# G8MainA_99_5x31.net
KiCad netlist of a schematic drawn in EAGLE
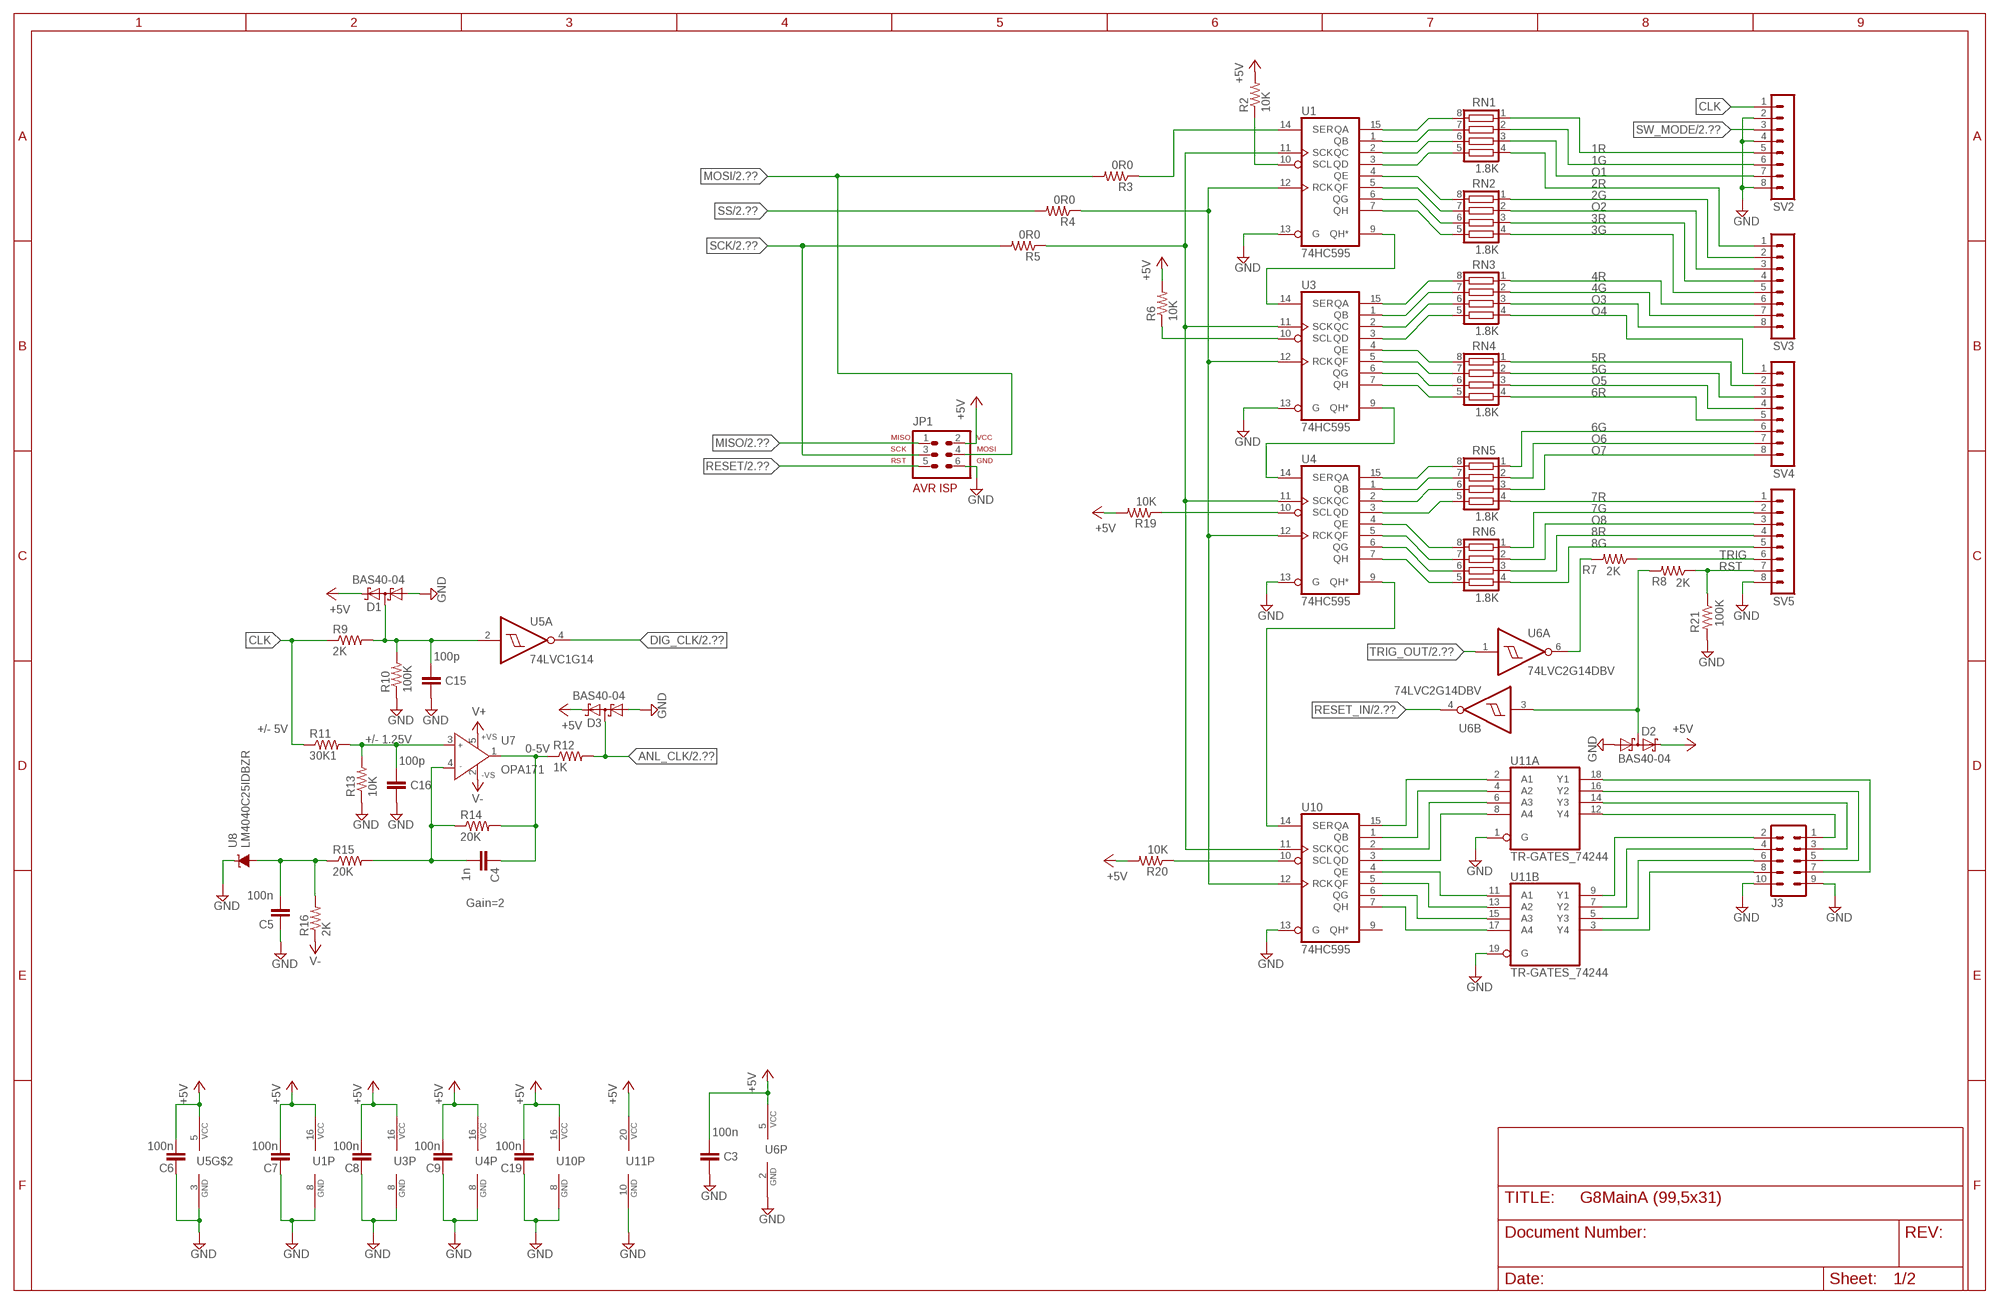
[diagram p0: schematic, sheet 1]
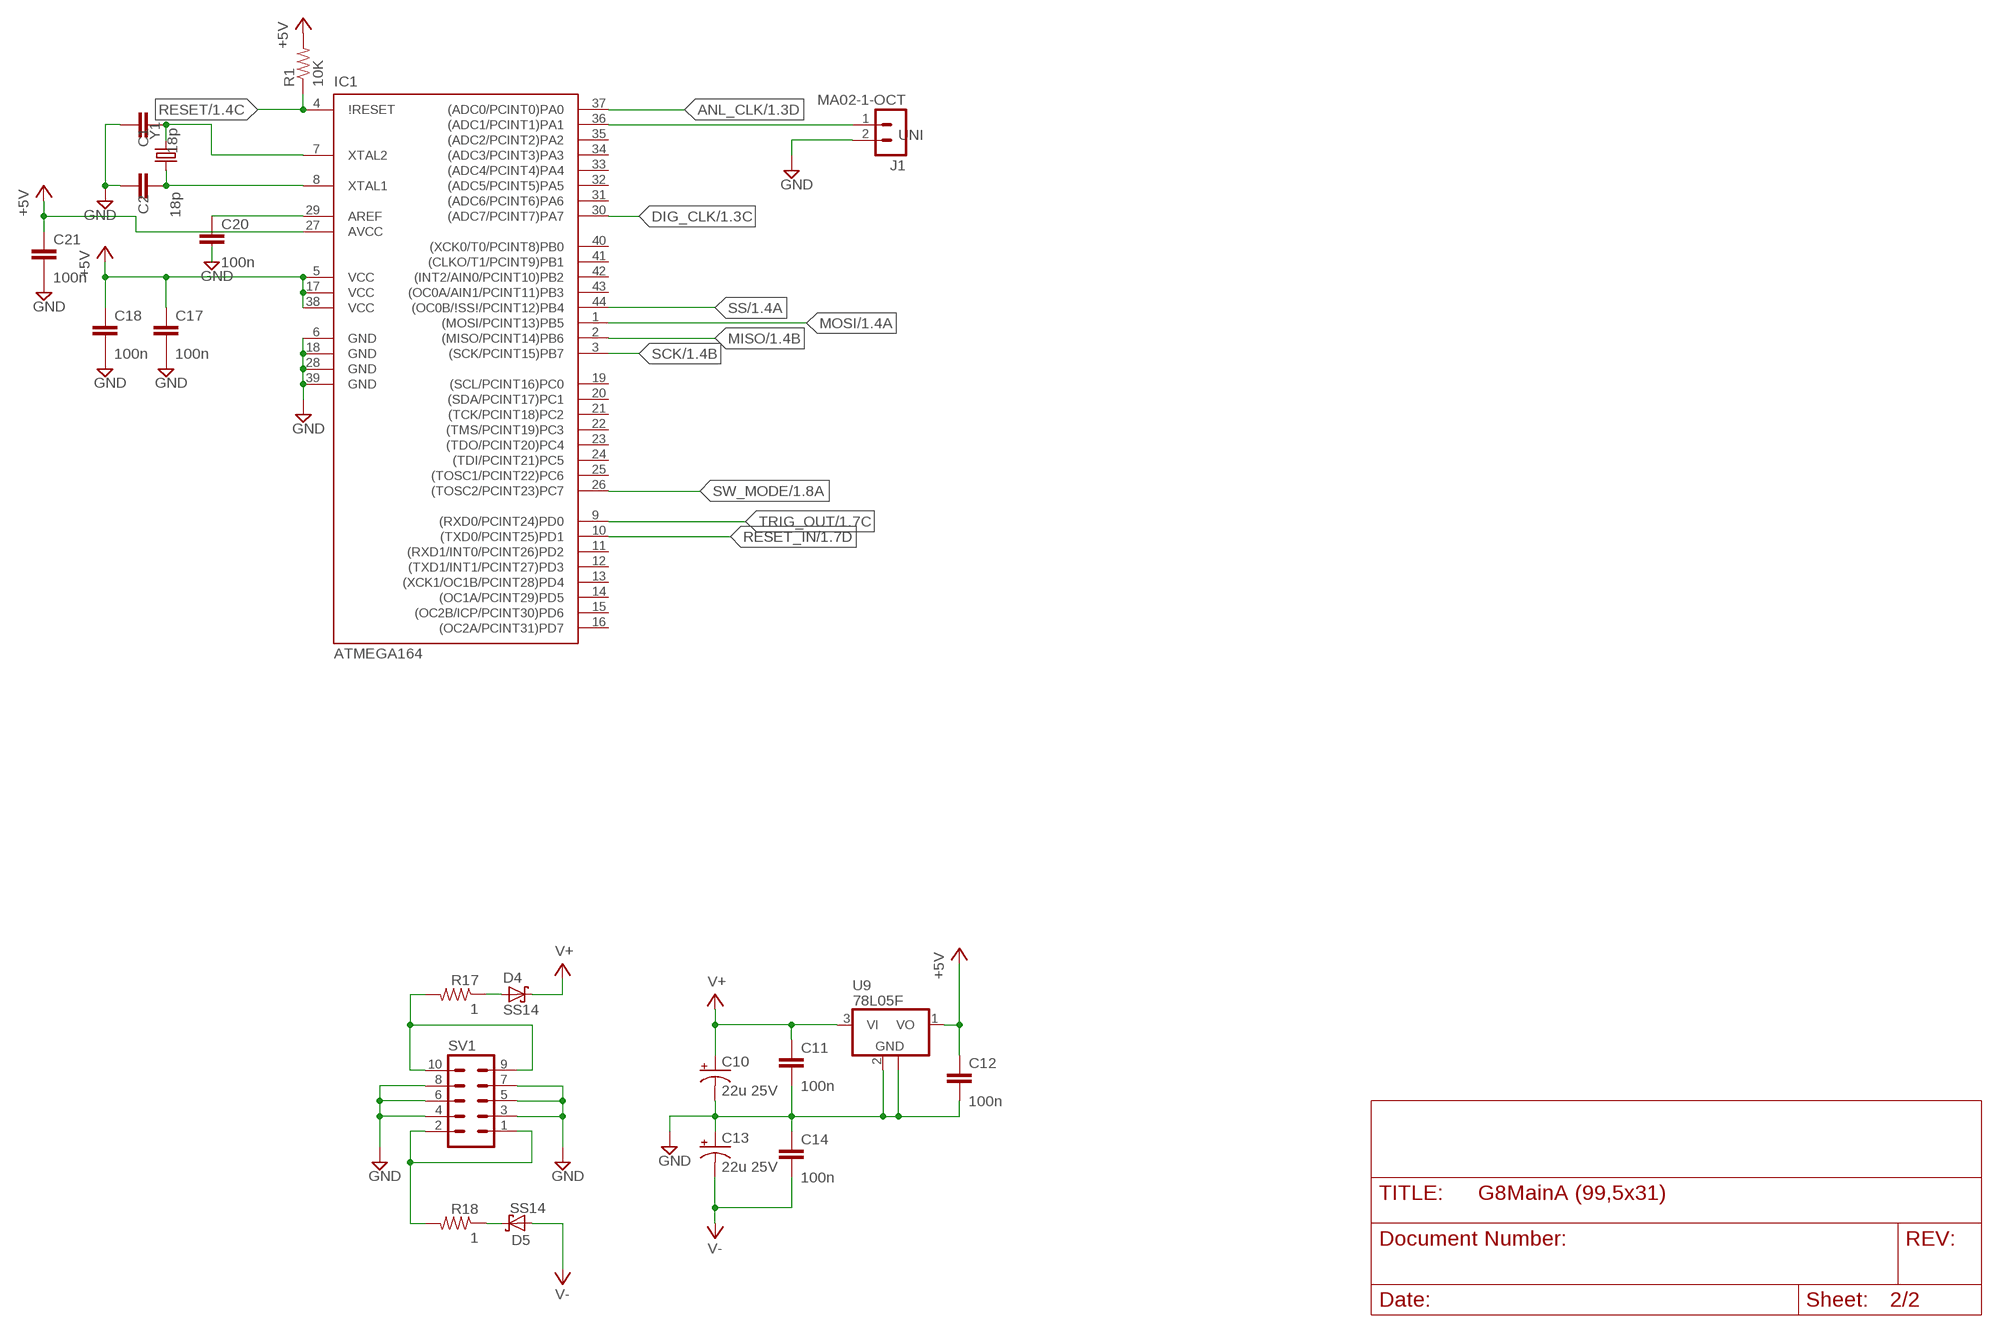
[diagram p1: schematic, sheet 2]

(export (version "E")
  (design (tool "Eeschema 10.0.6"))
  (components
    (comp (ref "C1")
      (value "18p")
      (footprint "eagle-import:C0603")
      (libsource (lib "eagle-import") (part "C0603"))
    )
    (comp (ref "C2")
      (value "18p")
      (footprint "eagle-import:C0603")
      (libsource (lib "eagle-import") (part "C0603"))
    )
    (comp (ref "C10")
      (value "22u 25V")
      (footprint "eagle-import:PANASONIC_C")
      (libsource (lib "eagle-import") (part "CPOL-USC"))
    )
    (comp (ref "C11")
      (value "100n")
      (footprint "eagle-import:C0603")
      (libsource (lib "eagle-import") (part "C0603"))
    )
    (comp (ref "C12")
      (value "100n")
      (footprint "eagle-import:C0603")
      (libsource (lib "eagle-import") (part "C0603"))
    )
    (comp (ref "C13")
      (value "22u 25V")
      (footprint "eagle-import:PANASONIC_C")
      (libsource (lib "eagle-import") (part "CPOL-USC"))
    )
    (comp (ref "C14")
      (value "100n")
      (footprint "eagle-import:C0603")
      (libsource (lib "eagle-import") (part "C0603"))
    )
    (comp (ref "C17")
      (value "100n")
      (footprint "eagle-import:C0603")
      (libsource (lib "eagle-import") (part "C0603"))
    )
    (comp (ref "C18")
      (value "100n")
      (footprint "eagle-import:C0603")
      (libsource (lib "eagle-import") (part "C0603"))
    )
    (comp (ref "C20")
      (value "100n")
      (footprint "eagle-import:C0603")
      (libsource (lib "eagle-import") (part "C0603"))
    )
    (comp (ref "C21")
      (value "100n")
      (footprint "eagle-import:C0603")
      (libsource (lib "eagle-import") (part "C0603"))
    )
    (comp (ref "D4")
      (value "SS14")
      (footprint "eagle-import:SMA-DO214AC")
      (libsource (lib "eagle-import") (part "T100331"))
    )
    (comp (ref "D5")
      (value "SS14")
      (footprint "eagle-import:SMA-DO214AC")
      (libsource (lib "eagle-import") (part "T100331"))
    )
    (comp (ref "IC1")
      (value "ATMEGA164")
      (footprint "eagle-import:TQFP44")
      (libsource (lib "eagle-import") (part "MEGA164P/324P/644P-AU"))
    )
    (comp (ref "J1")
      (value "MA02-1-OCT")
      (footprint "eagle-import:MA02-1-OCT")
      (libsource (lib "eagle-import") (part "MA02-1-OCT"))
    )
    (comp (ref "R1")
      (value "10K")
      (footprint "eagle-import:R0603")
      (libsource (lib "eagle-import") (part "R0603"))
    )
    (comp (ref "R17")
      (value "1")
      (footprint "eagle-import:R0603")
      (libsource (lib "eagle-import") (part "R0603"))
    )
    (comp (ref "R18")
      (value "1")
      (footprint "eagle-import:R0603")
      (libsource (lib "eagle-import") (part "R0603"))
    )
    (comp (ref "SV1")
      (value "MA05-2")
      (footprint "eagle-import:MA05-2")
      (libsource (lib "eagle-import") (part "MA05-2"))
    )
    (comp (ref "U9")
      (value "78L05F")
      (footprint "eagle-import:SOT89")
      (libsource (lib "eagle-import") (part "78LF05"))
    )
    (comp (ref "Y1")
      (value "CRYSTALHC49UV")
      (footprint "eagle-import:HC49U-V")
      (libsource (lib "eagle-import") (part "CRYSTALHC49UV"))
    )
    (comp (ref "C3")
      (value "100n")
      (footprint "eagle-import:C0603")
      (libsource (lib "eagle-import") (part "C0603"))
    )
    (comp (ref "C4")
      (value "1n")
      (footprint "eagle-import:C0603")
      (libsource (lib "eagle-import") (part "C0603"))
    )
    (comp (ref "C5")
      (value "100n")
      (footprint "eagle-import:C0603")
      (libsource (lib "eagle-import") (part "C0603"))
    )
    (comp (ref "C6")
      (value "100n")
      (footprint "eagle-import:C0603")
      (libsource (lib "eagle-import") (part "C0603"))
    )
    (comp (ref "C7")
      (value "100n")
      (footprint "eagle-import:C0603")
      (libsource (lib "eagle-import") (part "C0603"))
    )
    (comp (ref "C8")
      (value "100n")
      (footprint "eagle-import:C0603")
      (libsource (lib "eagle-import") (part "C0603"))
    )
    (comp (ref "C9")
      (value "100n")
      (footprint "eagle-import:C0603")
      (libsource (lib "eagle-import") (part "C0603"))
    )
    (comp (ref "C15")
      (value "100p")
      (footprint "eagle-import:C0603")
      (libsource (lib "eagle-import") (part "C0603"))
    )
    (comp (ref "C16")
      (value "100p")
      (footprint "eagle-import:C0603")
      (libsource (lib "eagle-import") (part "C0603"))
    )
    (comp (ref "C19")
      (value "100n")
      (footprint "eagle-import:C0603")
      (libsource (lib "eagle-import") (part "C0603"))
    )
    (comp (ref "D1")
      (value "BAS40-04")
      (footprint "eagle-import:SOT23")
      (libsource (lib "eagle-import") (part "BAS40-04"))
    )
    (comp (ref "D2")
      (value "BAS40-04")
      (footprint "eagle-import:SOT23")
      (libsource (lib "eagle-import") (part "BAS40-04"))
    )
    (comp (ref "D3")
      (value "BAS40-04")
      (footprint "eagle-import:SOT23")
      (libsource (lib "eagle-import") (part "BAS40-04"))
    )
    (comp (ref "J3")
      (value "MA05-2")
      (footprint "eagle-import:MA05-2")
      (libsource (lib "eagle-import") (part "MA05-2"))
    )
    (comp (ref "JP1")
      (value "AVR-ISP-6VERT")
      (footprint "eagle-import:AVR-ISP-6")
      (libsource (lib "eagle-import") (part "AVR-ISP-6VERT"))
    )
    (comp (ref "R2")
      (value "10K")
      (footprint "eagle-import:R0603")
      (libsource (lib "eagle-import") (part "R0603"))
    )
    (comp (ref "R3")
      (value "0R0")
      (footprint "eagle-import:R0603")
      (libsource (lib "eagle-import") (part "R0603"))
    )
    (comp (ref "R4")
      (value "0R0")
      (footprint "eagle-import:R0603")
      (libsource (lib "eagle-import") (part "R0603"))
    )
    (comp (ref "R5")
      (value "0R0")
      (footprint "eagle-import:R0603")
      (libsource (lib "eagle-import") (part "R0603"))
    )
    (comp (ref "R6")
      (value "10K")
      (footprint "eagle-import:R0603")
      (libsource (lib "eagle-import") (part "R0603"))
    )
    (comp (ref "R7")
      (value "2K")
      (footprint "eagle-import:R0603")
      (libsource (lib "eagle-import") (part "R0603"))
    )
    (comp (ref "R8")
      (value "2K")
      (footprint "eagle-import:R0603")
      (libsource (lib "eagle-import") (part "R0603"))
    )
    (comp (ref "R9")
      (value "2K")
      (footprint "eagle-import:R0603")
      (libsource (lib "eagle-import") (part "R0603"))
    )
    (comp (ref "R10")
      (value "100K")
      (footprint "eagle-import:R0603")
      (libsource (lib "eagle-import") (part "R0603"))
    )
    (comp (ref "R11")
      (value "30K1")
      (footprint "eagle-import:R0603")
      (libsource (lib "eagle-import") (part "R0603"))
    )
    (comp (ref "R12")
      (value "1K")
      (footprint "eagle-import:R0603")
      (libsource (lib "eagle-import") (part "R0603"))
    )
    (comp (ref "R13")
      (value "10K")
      (footprint "eagle-import:R0603")
      (libsource (lib "eagle-import") (part "R0603"))
    )
    (comp (ref "R14")
      (value "20K")
      (footprint "eagle-import:R0603")
      (libsource (lib "eagle-import") (part "R0603"))
    )
    (comp (ref "R15")
      (value "20K")
      (footprint "eagle-import:R0603")
      (libsource (lib "eagle-import") (part "R0603"))
    )
    (comp (ref "R16")
      (value "2K")
      (footprint "eagle-import:R0603")
      (libsource (lib "eagle-import") (part "R0603"))
    )
    (comp (ref "R19")
      (value "10K")
      (footprint "eagle-import:R0603")
      (libsource (lib "eagle-import") (part "R0603"))
    )
    (comp (ref "R20")
      (value "10K")
      (footprint "eagle-import:R0603")
      (libsource (lib "eagle-import") (part "R0603"))
    )
    (comp (ref "R21")
      (value "100K")
      (footprint "eagle-import:R0603")
      (libsource (lib "eagle-import") (part "R0603"))
    )
    (comp (ref "RN1")
      (value "1.8K")
      (footprint "eagle-import:CTS742C083")
      (libsource (lib "eagle-import") (part "CTS742C083"))
    )
    (comp (ref "RN2")
      (value "1.8K")
      (footprint "eagle-import:CTS742C083")
      (libsource (lib "eagle-import") (part "CTS742C083"))
    )
    (comp (ref "RN3")
      (value "1.8K")
      (footprint "eagle-import:CTS742C083")
      (libsource (lib "eagle-import") (part "CTS742C083"))
    )
    (comp (ref "RN4")
      (value "1.8K")
      (footprint "eagle-import:CTS742C083")
      (libsource (lib "eagle-import") (part "CTS742C083"))
    )
    (comp (ref "RN5")
      (value "1.8K")
      (footprint "eagle-import:CTS742C083")
      (fields (field (name "OC_FARNELL") "unknown") (field (name "OC_NEWARK") "unknown"))
      (libsource (lib "eagle-import") (part "CTS742C083"))
    )
    (comp (ref "RN6")
      (value "1.8K")
      (footprint "eagle-import:CTS742C083")
      (fields (field (name "OC_FARNELL") "unknown") (field (name "OC_NEWARK") "unknown"))
      (libsource (lib "eagle-import") (part "CTS742C083"))
    )
    (comp (ref "SV2")
      (value "MA08-1-O")
      (footprint "eagle-import:MA08-OCT")
      (libsource (lib "eagle-import") (part "MA08-1-O"))
    )
    (comp (ref "SV3")
      (value "MA08-1-O")
      (footprint "eagle-import:MA08-OCT")
      (libsource (lib "eagle-import") (part "MA08-1-O"))
    )
    (comp (ref "SV4")
      (value "MA08-1-O")
      (footprint "eagle-import:MA08-OCT")
      (libsource (lib "eagle-import") (part "MA08-1-O"))
    )
    (comp (ref "SV5")
      (value "MA08-1-O")
      (footprint "eagle-import:MA08-OCT")
      (libsource (lib "eagle-import") (part "MA08-1-O"))
    )
    (comp (ref "U1")
      (value "74HC595")
      (footprint "eagle-import:TSSOP16")
      (libsource (lib "eagle-import") (part "74595DT"))
    )
    (comp (ref "U3")
      (value "74HC595")
      (footprint "eagle-import:TSSOP16")
      (libsource (lib "eagle-import") (part "74595DT"))
    )
    (comp (ref "U4")
      (value "74HC595")
      (footprint "eagle-import:TSSOP16")
      (libsource (lib "eagle-import") (part "74595DT"))
    )
    (comp (ref "U5")
      (value "74LVC1G14")
      (footprint "eagle-import:SOT23-5L")
      (libsource (lib "eagle-import") (part "74LVC1G14"))
    )
    (comp (ref "U6")
      (value "74LVC2G14DBV")
      (footprint "eagle-import:SOT23-6")
      (libsource (lib "eagle-import") (part "74LVC2G14DBV"))
    )
    (comp (ref "U7")
      (value "OPA171")
      (footprint "eagle-import:SOT23-5")
      (fields (field (name "MPN") "AD8031ARTZ-REEL7"))
      (libsource (lib "eagle-import") (part "AD8031RJ"))
    )
    (comp (ref "U8")
      (value "LM4040C25IDBZR")
      (footprint "eagle-import:DBZ_R-PDSO-G3")
      (fields (field (name "MPN") "LM4041A12IDBZR"))
      (libsource (lib "eagle-import") (part "LM4041DBZA12"))
    )
    (comp (ref "U10")
      (value "74HC595")
      (footprint "eagle-import:TSSOP16")
      (libsource (lib "eagle-import") (part "74595DT"))
    )
    (comp (ref "U11")
      (value "TR-GATES_74244")
      (footprint "eagle-import:TR-GATES_TSSOP20")
      (libsource (lib "eagle-import") (part "TR-GATES_74244"))
    )
  )
  (nets
    (net (code "1") (name "+5V") (class "Default")
      (node (ref "C12") (pin "1") (pinfunction "1_1") (pintype "passive"))
      (node (ref "C17") (pin "1") (pinfunction "1_1") (pintype "passive"))
      (node (ref "C18") (pin "1") (pinfunction "1_1") (pintype "passive"))
      (node (ref "C19") (pin "2") (pinfunction "2_2") (pintype "passive"))
      (node (ref "C21") (pin "1") (pinfunction "1_1") (pintype "passive"))
      (node (ref "C3") (pin "2") (pinfunction "2_2") (pintype "passive"))
      (node (ref "C6") (pin "2") (pinfunction "2_2") (pintype "passive"))
      (node (ref "C7") (pin "2") (pinfunction "2_2") (pintype "passive"))
      (node (ref "C8") (pin "2") (pinfunction "2_2") (pintype "passive"))
      (node (ref "C9") (pin "2") (pinfunction "2_2") (pintype "passive"))
      (node (ref "D1") (pin "2") (pinfunction "C2_2") (pintype "passive"))
      (node (ref "D2") (pin "2") (pinfunction "C2_2") (pintype "passive"))
      (node (ref "D3") (pin "2") (pinfunction "C2_2") (pintype "passive"))
      (node (ref "IC1") (pin "17") (pinfunction "VCC_17") (pintype "power_in"))
      (node (ref "IC1") (pin "27") (pinfunction "AVCC_27") (pintype "power_in"))
      (node (ref "IC1") (pin "38") (pinfunction "VCC_38") (pintype "power_in"))
      (node (ref "IC1") (pin "5") (pinfunction "VCC_5") (pintype "power_in"))
      (node (ref "JP1") (pin "2") (pinfunction "2_2") (pintype "passive"))
      (node (ref "R1") (pin "2") (pinfunction "2_2") (pintype "passive"))
      (node (ref "R19") (pin "2") (pinfunction "2_2") (pintype "passive"))
      (node (ref "R2") (pin "2") (pinfunction "2_2") (pintype "passive"))
      (node (ref "R20") (pin "2") (pinfunction "2_2") (pintype "passive"))
      (node (ref "R6") (pin "2") (pinfunction "2_2") (pintype "passive"))
      (node (ref "U1") (pin "16") (pinfunction "VCC_16") (pintype "power_in"))
      (node (ref "U10") (pin "16") (pinfunction "VCC_16") (pintype "power_in"))
      (node (ref "U11") (pin "20") (pinfunction "VCC_20") (pintype "power_in"))
      (node (ref "U3") (pin "16") (pinfunction "VCC_16") (pintype "power_in"))
      (node (ref "U4") (pin "16") (pinfunction "VCC_16") (pintype "power_in"))
      (node (ref "U5") (pin "5") (pinfunction "VCC_5") (pintype "power_in"))
      (node (ref "U6") (pin "5") (pinfunction "VCC_5") (pintype "power_in"))
      (node (ref "U9") (pin "1") (pinfunction "VO_1") (pintype "passive"))
    )
    (net (code "2") (name "ANL_CLK") (class "Default")
      (node (ref "D3") (pin "3") (pinfunction "C1A2_3") (pintype "passive"))
      (node (ref "IC1") (pin "37") (pinfunction "(ADC0/PCINT0)PA0_37") (pintype "bidirectional"))
      (node (ref "R12") (pin "2") (pinfunction "2_2") (pintype "passive"))
    )
    (net (code "3") (name "CLK") (class "Default")
      (node (ref "R11") (pin "1") (pinfunction "1_1") (pintype "passive"))
      (node (ref "R9") (pin "1") (pinfunction "1_1") (pintype "passive"))
      (node (ref "SV2") (pin "1") (pinfunction "1_1") (pintype "passive"))
    )
    (net (code "4") (name "DIG_CLK") (class "Default")
      (node (ref "IC1") (pin "30") (pinfunction "(ADC7/PCINT7)PA7_30") (pintype "bidirectional"))
      (node (ref "U5") (pin "4") (pinfunction "O_4") (pintype "output"))
    )
    (net (code "5") (name "GND") (class "Default")
      (node (ref "C1") (pin "1") (pinfunction "1_1") (pintype "passive"))
      (node (ref "C10") (pin "-") (pinfunction "-_-") (pintype "passive"))
      (node (ref "C11") (pin "2") (pinfunction "2_2") (pintype "passive"))
      (node (ref "C12") (pin "2") (pinfunction "2_2") (pintype "passive"))
      (node (ref "C13") (pin "+") (pinfunction "+_+") (pintype "passive"))
      (node (ref "C14") (pin "1") (pinfunction "1_1") (pintype "passive"))
      (node (ref "C15") (pin "1") (pinfunction "1_1") (pintype "passive"))
      (node (ref "C16") (pin "1") (pinfunction "1_1") (pintype "passive"))
      (node (ref "C17") (pin "2") (pinfunction "2_2") (pintype "passive"))
      (node (ref "C18") (pin "2") (pinfunction "2_2") (pintype "passive"))
      (node (ref "C19") (pin "1") (pinfunction "1_1") (pintype "passive"))
      (node (ref "C2") (pin "1") (pinfunction "1_1") (pintype "passive"))
      (node (ref "C20") (pin "2") (pinfunction "2_2") (pintype "passive"))
      (node (ref "C21") (pin "2") (pinfunction "2_2") (pintype "passive"))
      (node (ref "C3") (pin "1") (pinfunction "1_1") (pintype "passive"))
      (node (ref "C5") (pin "1") (pinfunction "1_1") (pintype "passive"))
      (node (ref "C6") (pin "1") (pinfunction "1_1") (pintype "passive"))
      (node (ref "C7") (pin "1") (pinfunction "1_1") (pintype "passive"))
      (node (ref "C8") (pin "1") (pinfunction "1_1") (pintype "passive"))
      (node (ref "C9") (pin "1") (pinfunction "1_1") (pintype "passive"))
      (node (ref "D1") (pin "1") (pinfunction "A1_1") (pintype "passive"))
      (node (ref "D2") (pin "1") (pinfunction "A1_1") (pintype "passive"))
      (node (ref "D3") (pin "1") (pinfunction "A1_1") (pintype "passive"))
      (node (ref "IC1") (pin "18") (pinfunction "GND_18") (pintype "power_in"))
      (node (ref "IC1") (pin "28") (pinfunction "GND_28") (pintype "power_in"))
      (node (ref "IC1") (pin "39") (pinfunction "GND_39") (pintype "power_in"))
      (node (ref "IC1") (pin "6") (pinfunction "GND_6") (pintype "power_in"))
      (node (ref "J1") (pin "2") (pinfunction "2_2") (pintype "passive"))
      (node (ref "J3") (pin "10") (pinfunction "10_10") (pintype "passive"))
      (node (ref "J3") (pin "9") (pinfunction "9_9") (pintype "passive"))
      (node (ref "JP1") (pin "6") (pinfunction "6_6") (pintype "passive"))
      (node (ref "R10") (pin "1") (pinfunction "1_1") (pintype "passive"))
      (node (ref "R13") (pin "1") (pinfunction "1_1") (pintype "passive"))
      (node (ref "R21") (pin "2") (pinfunction "2_2") (pintype "passive"))
      (node (ref "SV1") (pin "3") (pinfunction "3_3") (pintype "passive"))
      (node (ref "SV1") (pin "4") (pinfunction "4_4") (pintype "passive"))
      (node (ref "SV1") (pin "5") (pinfunction "5_5") (pintype "passive"))
      (node (ref "SV1") (pin "6") (pinfunction "6_6") (pintype "passive"))
      (node (ref "SV1") (pin "7") (pinfunction "7_7") (pintype "passive"))
      (node (ref "SV1") (pin "8") (pinfunction "8_8") (pintype "passive"))
      (node (ref "SV2") (pin "2") (pinfunction "2_2") (pintype "passive"))
      (node (ref "SV2") (pin "4") (pinfunction "4_4") (pintype "passive"))
      (node (ref "SV2") (pin "8") (pinfunction "8_8") (pintype "passive"))
      (node (ref "SV5") (pin "8") (pinfunction "8_8") (pintype "passive"))
      (node (ref "U1") (pin "13") (pinfunction "G_13") (pintype "input"))
      (node (ref "U1") (pin "8") (pinfunction "GND_8") (pintype "power_in"))
      (node (ref "U10") (pin "13") (pinfunction "G_13") (pintype "input"))
      (node (ref "U10") (pin "8") (pinfunction "GND_8") (pintype "power_in"))
      (node (ref "U11") (pin "1") (pinfunction "G_1") (pintype "input"))
      (node (ref "U11") (pin "10") (pinfunction "GND_10") (pintype "power_in"))
      (node (ref "U11") (pin "19") (pinfunction "G_19") (pintype "input"))
      (node (ref "U3") (pin "13") (pinfunction "G_13") (pintype "input"))
      (node (ref "U3") (pin "8") (pinfunction "GND_8") (pintype "power_in"))
      (node (ref "U4") (pin "13") (pinfunction "G_13") (pintype "input"))
      (node (ref "U4") (pin "8") (pinfunction "GND_8") (pintype "power_in"))
      (node (ref "U5") (pin "3") (pinfunction "GND_3") (pintype "power_in"))
      (node (ref "U6") (pin "2") (pinfunction "GND_2") (pintype "power_in"))
      (node (ref "U8") (pin "1") (pinfunction "C_1") (pintype "passive"))
      (node (ref "U9") (pin "2") (pinfunction "GND_2") (pintype "passive"))
      (node (ref "U9") (pin "2@1") (pinfunction "GND_2@1") (pintype "passive"))
    )
    (net (code "6") (name "MISO") (class "Default")
      (node (ref "IC1") (pin "2") (pinfunction "(MISO/PCINT14)PB6_2") (pintype "bidirectional"))
      (node (ref "JP1") (pin "1") (pinfunction "1_1") (pintype "passive"))
    )
    (net (code "7") (name "MOSI") (class "Default")
      (node (ref "IC1") (pin "1") (pinfunction "(MOSI/PCINT13)PB5_1") (pintype "bidirectional"))
      (node (ref "JP1") (pin "4") (pinfunction "4_4") (pintype "passive"))
      (node (ref "R3") (pin "2") (pinfunction "2_2") (pintype "passive"))
    )
    (net (code "8") (name "Net-(D1-C1A2)") (class "Default")
      (node (ref "C15") (pin "2") (pinfunction "2_2") (pintype "passive"))
      (node (ref "D1") (pin "3") (pinfunction "C1A2_3") (pintype "passive"))
      (node (ref "R10") (pin "2") (pinfunction "2_2") (pintype "passive"))
      (node (ref "R9") (pin "2") (pinfunction "2_2") (pintype "passive"))
      (node (ref "U5") (pin "2") (pinfunction "I_2") (pintype "input"))
    )
    (net (code "9") (name "Net-(D2-C1A2)") (class "Default")
      (node (ref "D2") (pin "3") (pinfunction "C1A2_3") (pintype "passive"))
      (node (ref "R8") (pin "2") (pinfunction "2_2") (pintype "passive"))
      (node (ref "U6") (pin "3") (pinfunction "I_3") (pintype "input"))
    )
    (net (code "10") (name "Net-(D4-PadA)") (class "Default")
      (node (ref "D4") (pin "A") (pinfunction "A_A") (pintype "passive"))
      (node (ref "R17") (pin "1") (pinfunction "1_1") (pintype "passive"))
    )
    (net (code "11") (name "Net-(D5-C)") (class "Default")
      (node (ref "D5") (pin "K") (pinfunction "C_K") (pintype "passive"))
      (node (ref "R18") (pin "1") (pinfunction "1_1") (pintype "passive"))
    )
    (net (code "12") (name "Net-(IC1-(ADC1{slash}PCINT1)PA1)") (class "Default")
      (node (ref "IC1") (pin "36") (pinfunction "(ADC1/PCINT1)PA1_36") (pintype "bidirectional"))
      (node (ref "J1") (pin "1") (pinfunction "1_1") (pintype "passive"))
    )
    (net (code "13") (name "Net-(IC1-AREF)") (class "Default")
      (node (ref "C20") (pin "1") (pinfunction "1_1") (pintype "passive"))
      (node (ref "IC1") (pin "29") (pinfunction "AREF_29") (pintype "power_in"))
    )
    (net (code "14") (name "Net-(IC1-XTAL1)") (class "Default")
      (node (ref "C2") (pin "2") (pinfunction "2_2") (pintype "passive"))
      (node (ref "IC1") (pin "8") (pinfunction "XTAL1_8") (pintype "input"))
      (node (ref "Y1") (pin "1") (pinfunction "1_1") (pintype "passive"))
    )
    (net (code "15") (name "Net-(IC1-XTAL2)") (class "Default")
      (node (ref "C1") (pin "2") (pinfunction "2_2") (pintype "passive"))
      (node (ref "IC1") (pin "7") (pinfunction "XTAL2_7") (pintype "output"))
      (node (ref "Y1") (pin "2") (pinfunction "2_2") (pintype "passive"))
    )
    (net (code "16") (name "Net-(R7-Pad1)") (class "Default")
      (node (ref "R7") (pin "1") (pinfunction "1_1") (pintype "passive"))
      (node (ref "SV5") (pin "6") (pinfunction "6_6") (pintype "passive"))
    )
    (net (code "17") (name "Net-(R17-Pad2)") (class "Default")
      (node (ref "R17") (pin "2") (pinfunction "2_2") (pintype "passive"))
      (node (ref "SV1") (pin "10") (pinfunction "10_10") (pintype "passive"))
      (node (ref "SV1") (pin "9") (pinfunction "9_9") (pintype "passive"))
    )
    (net (code "18") (name "Net-(R18-Pad2)") (class "Default")
      (node (ref "R18") (pin "2") (pinfunction "2_2") (pintype "passive"))
      (node (ref "SV1") (pin "1") (pinfunction "1_1") (pintype "passive"))
      (node (ref "SV1") (pin "2") (pinfunction "2_2") (pintype "passive"))
    )
    (net (code "19") (name "Net-(R21-Pad1)") (class "Default")
      (node (ref "R21") (pin "1") (pinfunction "1_1") (pintype "passive"))
      (node (ref "R8") (pin "1") (pinfunction "1_1") (pintype "passive"))
      (node (ref "SV5") (pin "7") (pinfunction "7_7") (pintype "passive"))
    )
    (net (code "20") (name "Net-(RN1-Pad1)") (class "Default")
      (node (ref "RN1") (pin "1") (pinfunction "1_1") (pintype "passive"))
      (node (ref "SV2") (pin "5") (pinfunction "5_5") (pintype "passive"))
    )
    (net (code "21") (name "Net-(RN1-Pad2)") (class "Default")
      (node (ref "RN1") (pin "2") (pinfunction "2_2") (pintype "passive"))
      (node (ref "SV2") (pin "6") (pinfunction "6_6") (pintype "passive"))
    )
    (net (code "22") (name "Net-(RN1-Pad3)") (class "Default")
      (node (ref "RN1") (pin "3") (pinfunction "3_3") (pintype "passive"))
      (node (ref "SV2") (pin "7") (pinfunction "7_7") (pintype "passive"))
    )
    (net (code "23") (name "Net-(RN1-Pad4)") (class "Default")
      (node (ref "RN1") (pin "4") (pinfunction "4_4") (pintype "passive"))
      (node (ref "SV3") (pin "1") (pinfunction "1_1") (pintype "passive"))
    )
    (net (code "24") (name "Net-(RN2-Pad1)") (class "Default")
      (node (ref "RN2") (pin "1") (pinfunction "1_1") (pintype "passive"))
      (node (ref "SV3") (pin "2") (pinfunction "2_2") (pintype "passive"))
    )
    (net (code "25") (name "Net-(RN2-Pad2)") (class "Default")
      (node (ref "RN2") (pin "2") (pinfunction "2_2") (pintype "passive"))
      (node (ref "SV3") (pin "3") (pinfunction "3_3") (pintype "passive"))
    )
    (net (code "26") (name "Net-(RN2-Pad3)") (class "Default")
      (node (ref "RN2") (pin "3") (pinfunction "3_3") (pintype "passive"))
      (node (ref "SV3") (pin "4") (pinfunction "4_4") (pintype "passive"))
    )
    (net (code "27") (name "Net-(RN2-Pad4)") (class "Default")
      (node (ref "RN2") (pin "4") (pinfunction "4_4") (pintype "passive"))
      (node (ref "SV3") (pin "5") (pinfunction "5_5") (pintype "passive"))
    )
    (net (code "28") (name "Net-(RN3-Pad1)") (class "Default")
      (node (ref "RN3") (pin "1") (pinfunction "1_1") (pintype "passive"))
      (node (ref "SV3") (pin "6") (pinfunction "6_6") (pintype "passive"))
    )
    (net (code "29") (name "Net-(RN3-Pad2)") (class "Default")
      (node (ref "RN3") (pin "2") (pinfunction "2_2") (pintype "passive"))
      (node (ref "SV3") (pin "7") (pinfunction "7_7") (pintype "passive"))
    )
    (net (code "30") (name "Net-(RN3-Pad3)") (class "Default")
      (node (ref "RN3") (pin "3") (pinfunction "3_3") (pintype "passive"))
      (node (ref "SV3") (pin "8") (pinfunction "8_8") (pintype "passive"))
    )
    (net (code "31") (name "Net-(RN3-Pad4)") (class "Default")
      (node (ref "RN3") (pin "4") (pinfunction "4_4") (pintype "passive"))
      (node (ref "SV4") (pin "1") (pinfunction "1_1") (pintype "passive"))
    )
    (net (code "32") (name "Net-(RN4-Pad1)") (class "Default")
      (node (ref "RN4") (pin "1") (pinfunction "1_1") (pintype "passive"))
      (node (ref "SV4") (pin "2") (pinfunction "2_2") (pintype "passive"))
    )
    (net (code "33") (name "Net-(RN4-Pad2)") (class "Default")
      (node (ref "RN4") (pin "2") (pinfunction "2_2") (pintype "passive"))
      (node (ref "SV4") (pin "3") (pinfunction "3_3") (pintype "passive"))
    )
    (net (code "34") (name "Net-(RN4-Pad3)") (class "Default")
      (node (ref "RN4") (pin "3") (pinfunction "3_3") (pintype "passive"))
      (node (ref "SV4") (pin "4") (pinfunction "4_4") (pintype "passive"))
    )
    (net (code "35") (name "Net-(RN4-Pad4)") (class "Default")
      (node (ref "RN4") (pin "4") (pinfunction "4_4") (pintype "passive"))
      (node (ref "SV4") (pin "5") (pinfunction "5_5") (pintype "passive"))
    )
    (net (code "36") (name "Net-(RN5-Pad1)") (class "Default")
      (node (ref "RN5") (pin "1") (pinfunction "1_1") (pintype "passive"))
      (node (ref "SV4") (pin "6") (pinfunction "6_6") (pintype "passive"))
    )
    (net (code "37") (name "Net-(RN5-Pad2)") (class "Default")
      (node (ref "RN5") (pin "2") (pinfunction "2_2") (pintype "passive"))
      (node (ref "SV4") (pin "7") (pinfunction "7_7") (pintype "passive"))
    )
    (net (code "38") (name "Net-(RN5-Pad3)") (class "Default")
      (node (ref "RN5") (pin "3") (pinfunction "3_3") (pintype "passive"))
      (node (ref "SV4") (pin "8") (pinfunction "8_8") (pintype "passive"))
    )
    (net (code "39") (name "Net-(RN5-Pad4)") (class "Default")
      (node (ref "RN5") (pin "4") (pinfunction "4_4") (pintype "passive"))
      (node (ref "SV5") (pin "1") (pinfunction "1_1") (pintype "passive"))
    )
    (net (code "40") (name "Net-(RN6-Pad1)") (class "Default")
      (node (ref "RN6") (pin "1") (pinfunction "1_1") (pintype "passive"))
      (node (ref "SV5") (pin "2") (pinfunction "2_2") (pintype "passive"))
    )
    (net (code "41") (name "Net-(RN6-Pad2)") (class "Default")
      (node (ref "RN6") (pin "2") (pinfunction "2_2") (pintype "passive"))
      (node (ref "SV5") (pin "3") (pinfunction "3_3") (pintype "passive"))
    )
    (net (code "42") (name "Net-(RN6-Pad3)") (class "Default")
      (node (ref "RN6") (pin "3") (pinfunction "3_3") (pintype "passive"))
      (node (ref "SV5") (pin "4") (pinfunction "4_4") (pintype "passive"))
    )
    (net (code "43") (name "Net-(RN6-Pad4)") (class "Default")
      (node (ref "RN6") (pin "4") (pinfunction "4_4") (pintype "passive"))
      (node (ref "SV5") (pin "5") (pinfunction "5_5") (pintype "passive"))
    )
    (net (code "44") (name "Net-(U1A-QA)") (class "Default")
      (node (ref "RN1") (pin "8") (pinfunction "8_8") (pintype "passive"))
      (node (ref "U1") (pin "15") (pinfunction "QA_15") (pintype "tri_state"))
    )
    (net (code "45") (name "Net-(U1A-QB)") (class "Default")
      (node (ref "RN1") (pin "7") (pinfunction "7_7") (pintype "passive"))
      (node (ref "U1") (pin "1") (pinfunction "QB_1") (pintype "tri_state"))
    )
    (net (code "46") (name "Net-(U1A-QC)") (class "Default")
      (node (ref "RN1") (pin "6") (pinfunction "6_6") (pintype "passive"))
      (node (ref "U1") (pin "2") (pinfunction "QC_2") (pintype "tri_state"))
    )
    (net (code "47") (name "Net-(U1A-QD)") (class "Default")
      (node (ref "RN1") (pin "5") (pinfunction "5_5") (pintype "passive"))
      (node (ref "U1") (pin "3") (pinfunction "QD_3") (pintype "tri_state"))
    )
    (net (code "48") (name "Net-(U1A-QE)") (class "Default")
      (node (ref "RN2") (pin "8") (pinfunction "8_8") (pintype "passive"))
      (node (ref "U1") (pin "4") (pinfunction "QE_4") (pintype "tri_state"))
    )
    (net (code "49") (name "Net-(U1A-QF)") (class "Default")
      (node (ref "RN2") (pin "7") (pinfunction "7_7") (pintype "passive"))
      (node (ref "U1") (pin "5") (pinfunction "QF_5") (pintype "tri_state"))
    )
    (net (code "50") (name "Net-(U1A-QG)") (class "Default")
      (node (ref "RN2") (pin "6") (pinfunction "6_6") (pintype "passive"))
      (node (ref "U1") (pin "6") (pinfunction "QG_6") (pintype "tri_state"))
    )
    (net (code "51") (name "Net-(U1A-QH)") (class "Default")
      (node (ref "RN2") (pin "5") (pinfunction "5_5") (pintype "passive"))
      (node (ref "U1") (pin "7") (pinfunction "QH_7") (pintype "tri_state"))
    )
    (net (code "52") (name "Net-(U1A-QH*)") (class "Default")
      (node (ref "U1") (pin "9") (pinfunction "QH*_9") (pintype "tri_state"))
      (node (ref "U3") (pin "14") (pinfunction "SER_14") (pintype "input"))
    )
    (net (code "53") (name "Net-(U1A-SCL)") (class "Default")
      (node (ref "R2") (pin "1") (pinfunction "1_1") (pintype "passive"))
      (node (ref "U1") (pin "10") (pinfunction "SCL_10") (pintype "input"))
    )
    (net (code "54") (name "Net-(U1A-SER)") (class "Default")
      (node (ref "R3") (pin "1") (pinfunction "1_1") (pintype "passive"))
      (node (ref "U1") (pin "14") (pinfunction "SER_14") (pintype "input"))
    )
    (net (code "55") (name "Net-(U3A-QA)") (class "Default")
      (node (ref "RN3") (pin "8") (pinfunction "8_8") (pintype "passive"))
      (node (ref "U3") (pin "15") (pinfunction "QA_15") (pintype "tri_state"))
    )
    (net (code "56") (name "Net-(U3A-QB)") (class "Default")
      (node (ref "RN3") (pin "7") (pinfunction "7_7") (pintype "passive"))
      (node (ref "U3") (pin "1") (pinfunction "QB_1") (pintype "tri_state"))
    )
    (net (code "57") (name "Net-(U3A-QC)") (class "Default")
      (node (ref "RN3") (pin "6") (pinfunction "6_6") (pintype "passive"))
      (node (ref "U3") (pin "2") (pinfunction "QC_2") (pintype "tri_state"))
    )
    (net (code "58") (name "Net-(U3A-QD)") (class "Default")
      (node (ref "RN3") (pin "5") (pinfunction "5_5") (pintype "passive"))
      (node (ref "U3") (pin "3") (pinfunction "QD_3") (pintype "tri_state"))
    )
    (net (code "59") (name "Net-(U3A-QE)") (class "Default")
      (node (ref "RN4") (pin "8") (pinfunction "8_8") (pintype "passive"))
      (node (ref "U3") (pin "4") (pinfunction "QE_4") (pintype "tri_state"))
    )
    (net (code "60") (name "Net-(U3A-QF)") (class "Default")
      (node (ref "RN4") (pin "7") (pinfunction "7_7") (pintype "passive"))
      (node (ref "U3") (pin "5") (pinfunction "QF_5") (pintype "tri_state"))
    )
    (net (code "61") (name "Net-(U3A-QG)") (class "Default")
      (node (ref "RN4") (pin "6") (pinfunction "6_6") (pintype "passive"))
      (node (ref "U3") (pin "6") (pinfunction "QG_6") (pintype "tri_state"))
    )
    (net (code "62") (name "Net-(U3A-QH)") (class "Default")
      (node (ref "RN4") (pin "5") (pinfunction "5_5") (pintype "passive"))
      (node (ref "U3") (pin "7") (pinfunction "QH_7") (pintype "tri_state"))
    )
    (net (code "63") (name "Net-(U3A-QH*)") (class "Default")
      (node (ref "U3") (pin "9") (pinfunction "QH*_9") (pintype "tri_state"))
      (node (ref "U4") (pin "14") (pinfunction "SER_14") (pintype "input"))
    )
    (net (code "64") (name "Net-(U3A-SCL)") (class "Default")
      (node (ref "R6") (pin "1") (pinfunction "1_1") (pintype "passive"))
      (node (ref "U3") (pin "10") (pinfunction "SCL_10") (pintype "input"))
    )
    (net (code "65") (name "Net-(U4A-QA)") (class "Default")
      (node (ref "RN5") (pin "8") (pinfunction "8_8") (pintype "passive"))
      (node (ref "U4") (pin "15") (pinfunction "QA_15") (pintype "tri_state"))
    )
    (net (code "66") (name "Net-(U4A-QB)") (class "Default")
      (node (ref "RN5") (pin "7") (pinfunction "7_7") (pintype "passive"))
      (node (ref "U4") (pin "1") (pinfunction "QB_1") (pintype "tri_state"))
    )
    (net (code "67") (name "Net-(U4A-QC)") (class "Default")
      (node (ref "RN5") (pin "6") (pinfunction "6_6") (pintype "passive"))
      (node (ref "U4") (pin "2") (pinfunction "QC_2") (pintype "tri_state"))
    )
    (net (code "68") (name "Net-(U4A-QD)") (class "Default")
      (node (ref "RN5") (pin "5") (pinfunction "5_5") (pintype "passive"))
      (node (ref "U4") (pin "3") (pinfunction "QD_3") (pintype "tri_state"))
    )
    (net (code "69") (name "Net-(U4A-QE)") (class "Default")
      (node (ref "RN6") (pin "8") (pinfunction "8_8") (pintype "passive"))
      (node (ref "U4") (pin "4") (pinfunction "QE_4") (pintype "tri_state"))
    )
    (net (code "70") (name "Net-(U4A-QF)") (class "Default")
      (node (ref "RN6") (pin "7") (pinfunction "7_7") (pintype "passive"))
      (node (ref "U4") (pin "5") (pinfunction "QF_5") (pintype "tri_state"))
    )
    (net (code "71") (name "Net-(U4A-QG)") (class "Default")
      (node (ref "RN6") (pin "6") (pinfunction "6_6") (pintype "passive"))
      (node (ref "U4") (pin "6") (pinfunction "QG_6") (pintype "tri_state"))
    )
    (net (code "72") (name "Net-(U4A-QH)") (class "Default")
      (node (ref "RN6") (pin "5") (pinfunction "5_5") (pintype "passive"))
      (node (ref "U4") (pin "7") (pinfunction "QH_7") (pintype "tri_state"))
    )
    (net (code "73") (name "Net-(U4A-SCL)") (class "Default")
      (node (ref "R19") (pin "1") (pinfunction "1_1") (pintype "passive"))
      (node (ref "U4") (pin "10") (pinfunction "SCL_10") (pintype "input"))
    )
    (net (code "74") (name "Net-(U6A-O)") (class "Default")
      (node (ref "R7") (pin "2") (pinfunction "2_2") (pintype "passive"))
      (node (ref "U6") (pin "6") (pinfunction "O_6") (pintype "output"))
    )
    (net (code "75") (name "Net-(U7-IN+)") (class "Default")
      (node (ref "C16") (pin "2") (pinfunction "2_2") (pintype "passive"))
      (node (ref "R11") (pin "2") (pinfunction "2_2") (pintype "passive"))
      (node (ref "R13") (pin "2") (pinfunction "2_2") (pintype "passive"))
      (node (ref "U7") (pin "3") (pinfunction "IN+_3") (pintype "input"))
    )
    (net (code "76") (name "Net-(U7-IN-)") (class "Default")
      (node (ref "C4") (pin "2") (pinfunction "2_2") (pintype "passive"))
      (node (ref "R14") (pin "1") (pinfunction "1_1") (pintype "passive"))
      (node (ref "R15") (pin "2") (pinfunction "2_2") (pintype "passive"))
      (node (ref "U7") (pin "4") (pinfunction "IN-_4") (pintype "input"))
    )
    (net (code "77") (name "Net-(U7-OUT)") (class "Default")
      (node (ref "C4") (pin "1") (pinfunction "1_1") (pintype "passive"))
      (node (ref "R12") (pin "1") (pinfunction "1_1") (pintype "passive"))
      (node (ref "R14") (pin "2") (pinfunction "2_2") (pintype "passive"))
      (node (ref "U7") (pin "1") (pinfunction "OUT_1") (pintype "output"))
    )
    (net (code "78") (name "Net-(U8-A)") (class "Default")
      (node (ref "C5") (pin "2") (pinfunction "2_2") (pintype "passive"))
      (node (ref "R15") (pin "1") (pinfunction "1_1") (pintype "passive"))
      (node (ref "R16") (pin "2") (pinfunction "2_2") (pintype "passive"))
      (node (ref "U8") (pin "2") (pinfunction "A_2") (pintype "passive"))
    )
    (net (code "79") (name "Net-(U10A-QA)") (class "Default")
      (node (ref "U10") (pin "15") (pinfunction "QA_15") (pintype "tri_state"))
      (node (ref "U11") (pin "2") (pinfunction "A1_2") (pintype "input"))
    )
    (net (code "80") (name "Net-(U10A-QB)") (class "Default")
      (node (ref "U10") (pin "1") (pinfunction "QB_1") (pintype "tri_state"))
      (node (ref "U11") (pin "4") (pinfunction "A2_4") (pintype "input"))
    )
    (net (code "81") (name "Net-(U10A-QC)") (class "Default")
      (node (ref "U10") (pin "2") (pinfunction "QC_2") (pintype "tri_state"))
      (node (ref "U11") (pin "6") (pinfunction "A3_6") (pintype "input"))
    )
    (net (code "82") (name "Net-(U10A-QD)") (class "Default")
      (node (ref "U10") (pin "3") (pinfunction "QD_3") (pintype "tri_state"))
      (node (ref "U11") (pin "8") (pinfunction "A4_8") (pintype "input"))
    )
    (net (code "83") (name "Net-(U10A-QE)") (class "Default")
      (node (ref "U10") (pin "4") (pinfunction "QE_4") (pintype "tri_state"))
      (node (ref "U11") (pin "11") (pinfunction "A1_11") (pintype "input"))
    )
    (net (code "84") (name "Net-(U10A-QF)") (class "Default")
      (node (ref "U10") (pin "5") (pinfunction "QF_5") (pintype "tri_state"))
      (node (ref "U11") (pin "13") (pinfunction "A2_13") (pintype "input"))
    )
    (net (code "85") (name "Net-(U10A-QG)") (class "Default")
      (node (ref "U10") (pin "6") (pinfunction "QG_6") (pintype "tri_state"))
      (node (ref "U11") (pin "15") (pinfunction "A3_15") (pintype "input"))
    )
    (net (code "86") (name "Net-(U10A-QH)") (class "Default")
      (node (ref "U10") (pin "7") (pinfunction "QH_7") (pintype "tri_state"))
      (node (ref "U11") (pin "17") (pinfunction "A4_17") (pintype "input"))
    )
    (net (code "87") (name "Net-(U10A-RCK)") (class "Default")
      (node (ref "R4") (pin "1") (pinfunction "1_1") (pintype "passive"))
      (node (ref "U1") (pin "12") (pinfunction "RCK_12") (pintype "input"))
      (node (ref "U10") (pin "12") (pinfunction "RCK_12") (pintype "input"))
      (node (ref "U3") (pin "12") (pinfunction "RCK_12") (pintype "input"))
      (node (ref "U4") (pin "12") (pinfunction "RCK_12") (pintype "input"))
    )
    (net (code "88") (name "Net-(U10A-SCK)") (class "Default")
      (node (ref "R5") (pin "1") (pinfunction "1_1") (pintype "passive"))
      (node (ref "U1") (pin "11") (pinfunction "SCK_11") (pintype "input"))
      (node (ref "U10") (pin "11") (pinfunction "SCK_11") (pintype "input"))
      (node (ref "U3") (pin "11") (pinfunction "SCK_11") (pintype "input"))
      (node (ref "U4") (pin "11") (pinfunction "SCK_11") (pintype "input"))
    )
    (net (code "89") (name "Net-(U10A-SCL)") (class "Default")
      (node (ref "R20") (pin "1") (pinfunction "1_1") (pintype "passive"))
      (node (ref "U10") (pin "10") (pinfunction "SCL_10") (pintype "input"))
    )
    (net (code "90") (name "Net-(U10A-SER)") (class "Default")
      (node (ref "U10") (pin "14") (pinfunction "SER_14") (pintype "input"))
      (node (ref "U4") (pin "9") (pinfunction "QH*_9") (pintype "tri_state"))
    )
    (net (code "91") (name "Net-(U11A-Y1)") (class "Default")
      (node (ref "J3") (pin "7") (pinfunction "7_7") (pintype "passive"))
      (node (ref "U11") (pin "18") (pinfunction "Y1_18") (pintype "tri_state"))
    )
    (net (code "92") (name "Net-(U11A-Y2)") (class "Default")
      (node (ref "J3") (pin "5") (pinfunction "5_5") (pintype "passive"))
      (node (ref "U11") (pin "16") (pinfunction "Y2_16") (pintype "tri_state"))
    )
    (net (code "93") (name "Net-(U11A-Y3)") (class "Default")
      (node (ref "J3") (pin "3") (pinfunction "3_3") (pintype "passive"))
      (node (ref "U11") (pin "14") (pinfunction "Y3_14") (pintype "tri_state"))
    )
    (net (code "94") (name "Net-(U11A-Y4)") (class "Default")
      (node (ref "J3") (pin "1") (pinfunction "1_1") (pintype "passive"))
      (node (ref "U11") (pin "12") (pinfunction "Y4_12") (pintype "tri_state"))
    )
    (net (code "95") (name "Net-(U11B-Y1)") (class "Default")
      (node (ref "J3") (pin "2") (pinfunction "2_2") (pintype "passive"))
      (node (ref "U11") (pin "9") (pinfunction "Y1_9") (pintype "tri_state"))
    )
    (net (code "96") (name "Net-(U11B-Y2)") (class "Default")
      (node (ref "J3") (pin "4") (pinfunction "4_4") (pintype "passive"))
      (node (ref "U11") (pin "7") (pinfunction "Y2_7") (pintype "tri_state"))
    )
    (net (code "97") (name "Net-(U11B-Y3)") (class "Default")
      (node (ref "J3") (pin "6") (pinfunction "6_6") (pintype "passive"))
      (node (ref "U11") (pin "5") (pinfunction "Y3_5") (pintype "tri_state"))
    )
    (net (code "98") (name "Net-(U11B-Y4)") (class "Default")
      (node (ref "J3") (pin "8") (pinfunction "8_8") (pintype "passive"))
      (node (ref "U11") (pin "3") (pinfunction "Y4_3") (pintype "tri_state"))
    )
    (net (code "99") (name "RESET") (class "Default")
      (node (ref "IC1") (pin "4") (pinfunction "\\~{RESET}_4") (pintype "input"))
      (node (ref "JP1") (pin "5") (pinfunction "5_5") (pintype "passive"))
      (node (ref "R1") (pin "1") (pinfunction "1_1") (pintype "passive"))
    )
    (net (code "100") (name "RESET_IN") (class "Default")
      (node (ref "IC1") (pin "10") (pinfunction "(TXD0/PCINT25)PD1_10") (pintype "bidirectional"))
      (node (ref "U6") (pin "4") (pinfunction "O_4") (pintype "output"))
    )
    (net (code "101") (name "SCK") (class "Default")
      (node (ref "IC1") (pin "3") (pinfunction "(SCK/PCINT15)PB7_3") (pintype "bidirectional"))
      (node (ref "JP1") (pin "3") (pinfunction "3_3") (pintype "passive"))
      (node (ref "R5") (pin "2") (pinfunction "2_2") (pintype "passive"))
    )
    (net (code "102") (name "SS") (class "Default")
      (node (ref "IC1") (pin "44") (pinfunction "(OC0B/\\~{SS\\}/PCINT12)PB4_44") (pintype "bidirectional"))
      (node (ref "R4") (pin "2") (pinfunction "2_2") (pintype "passive"))
    )
    (net (code "103") (name "SW_MODE") (class "Default")
      (node (ref "IC1") (pin "26") (pinfunction "(TOSC2/PCINT23)PC7_26") (pintype "bidirectional"))
      (node (ref "SV2") (pin "3") (pinfunction "3_3") (pintype "passive"))
    )
    (net (code "104") (name "TRIG_OUT") (class "Default")
      (node (ref "IC1") (pin "9") (pinfunction "(RXD0/PCINT24)PD0_9") (pintype "bidirectional"))
      (node (ref "U6") (pin "1") (pinfunction "I_1") (pintype "input"))
    )
    (net (code "105") (name "V+") (class "Default")
      (node (ref "C10") (pin "+") (pinfunction "+_+") (pintype "passive"))
      (node (ref "C11") (pin "1") (pinfunction "1_1") (pintype "passive"))
      (node (ref "D4") (pin "K") (pinfunction "C_K") (pintype "passive"))
      (node (ref "U7") (pin "5") (pinfunction "+VS_5") (pintype "input"))
      (node (ref "U9") (pin "3") (pinfunction "VI_3") (pintype "input"))
    )
    (net (code "106") (name "V-") (class "Default")
      (node (ref "C13") (pin "-") (pinfunction "-_-") (pintype "passive"))
      (node (ref "C14") (pin "2") (pinfunction "2_2") (pintype "passive"))
      (node (ref "D5") (pin "A") (pinfunction "A_A") (pintype "passive"))
      (node (ref "R16") (pin "1") (pinfunction "1_1") (pintype "passive"))
      (node (ref "U7") (pin "2") (pinfunction "-VS_2") (pintype "input"))
    )
    (net (code "107") (name "unconnected-(IC1-(ADC2{slash}PCINT2)PA2-Pad35)") (class "Default")
      (node (ref "IC1") (pin "35") (pinfunction "(ADC2/PCINT2)PA2_35") (pintype "bidirectional"))
    )
    (net (code "108") (name "unconnected-(IC1-(ADC3{slash}PCINT3)PA3-Pad34)") (class "Default")
      (node (ref "IC1") (pin "34") (pinfunction "(ADC3/PCINT3)PA3_34") (pintype "bidirectional"))
    )
    (net (code "109") (name "unconnected-(IC1-(ADC4{slash}PCINT4)PA4-Pad33)") (class "Default")
      (node (ref "IC1") (pin "33") (pinfunction "(ADC4/PCINT4)PA4_33") (pintype "bidirectional"))
    )
    (net (code "110") (name "unconnected-(IC1-(ADC5{slash}PCINT5)PA5-Pad32)") (class "Default")
      (node (ref "IC1") (pin "32") (pinfunction "(ADC5/PCINT5)PA5_32") (pintype "bidirectional"))
    )
    (net (code "111") (name "unconnected-(IC1-(ADC6{slash}PCINT6)PA6-Pad31)") (class "Default")
      (node (ref "IC1") (pin "31") (pinfunction "(ADC6/PCINT6)PA6_31") (pintype "bidirectional"))
    )
    (net (code "112") (name "unconnected-(IC1-(CLKO{slash}T1{slash}PCINT9)PB1-Pad41)") (class "Default")
      (node (ref "IC1") (pin "41") (pinfunction "(CLKO/T1/PCINT9)PB1_41") (pintype "bidirectional"))
    )
    (net (code "113") (name "unconnected-(IC1-(INT2{slash}AIN0{slash}PCINT10)PB2-Pad42)") (class "Default")
      (node (ref "IC1") (pin "42") (pinfunction "(INT2/AIN0/PCINT10)PB2_42") (pintype "bidirectional"))
    )
    (net (code "114") (name "unconnected-(IC1-(OC0A{slash}AIN1{slash}PCINT11)PB3-Pad43)") (class "Default")
      (node (ref "IC1") (pin "43") (pinfunction "(OC0A/AIN1/PCINT11)PB3_43") (pintype "bidirectional"))
    )
    (net (code "115") (name "unconnected-(IC1-(OC1A{slash}PCINT29)PD5-Pad14)") (class "Default")
      (node (ref "IC1") (pin "14") (pinfunction "(OC1A/PCINT29)PD5_14") (pintype "bidirectional"))
    )
    (net (code "116") (name "unconnected-(IC1-(OC2A{slash}PCINT31)PD7-Pad16)") (class "Default")
      (node (ref "IC1") (pin "16") (pinfunction "(OC2A/PCINT31)PD7_16") (pintype "bidirectional"))
    )
    (net (code "117") (name "unconnected-(IC1-(OC2B{slash}ICP{slash}PCINT30)PD6-Pad15)") (class "Default")
      (node (ref "IC1") (pin "15") (pinfunction "(OC2B/ICP/PCINT30)PD6_15") (pintype "bidirectional"))
    )
    (net (code "118") (name "unconnected-(IC1-(RXD1{slash}INT0{slash}PCINT26)PD2-Pad11)") (class "Default")
      (node (ref "IC1") (pin "11") (pinfunction "(RXD1/INT0/PCINT26)PD2_11") (pintype "bidirectional"))
    )
    (net (code "119") (name "unconnected-(IC1-(SCL{slash}PCINT16)PC0-Pad19)") (class "Default")
      (node (ref "IC1") (pin "19") (pinfunction "(SCL/PCINT16)PC0_19") (pintype "bidirectional"))
    )
    (net (code "120") (name "unconnected-(IC1-(SDA{slash}PCINT17)PC1-Pad20)") (class "Default")
      (node (ref "IC1") (pin "20") (pinfunction "(SDA/PCINT17)PC1_20") (pintype "bidirectional"))
    )
    (net (code "121") (name "unconnected-(IC1-(TCK{slash}PCINT18)PC2-Pad21)") (class "Default")
      (node (ref "IC1") (pin "21") (pinfunction "(TCK/PCINT18)PC2_21") (pintype "bidirectional"))
    )
    (net (code "122") (name "unconnected-(IC1-(TDI{slash}PCINT21)PC5-Pad24)") (class "Default")
      (node (ref "IC1") (pin "24") (pinfunction "(TDI/PCINT21)PC5_24") (pintype "bidirectional"))
    )
    (net (code "123") (name "unconnected-(IC1-(TDO{slash}PCINT20)PC4-Pad23)") (class "Default")
      (node (ref "IC1") (pin "23") (pinfunction "(TDO/PCINT20)PC4_23") (pintype "bidirectional"))
    )
    (net (code "124") (name "unconnected-(IC1-(TMS{slash}PCINT19)PC3-Pad22)") (class "Default")
      (node (ref "IC1") (pin "22") (pinfunction "(TMS/PCINT19)PC3_22") (pintype "bidirectional"))
    )
    (net (code "125") (name "unconnected-(IC1-(TOSC1{slash}PCINT22)PC6-Pad25)") (class "Default")
      (node (ref "IC1") (pin "25") (pinfunction "(TOSC1/PCINT22)PC6_25") (pintype "bidirectional"))
    )
    (net (code "126") (name "unconnected-(IC1-(TXD1{slash}INT1{slash}PCINT27)PD3-Pad12)") (class "Default")
      (node (ref "IC1") (pin "12") (pinfunction "(TXD1/INT1/PCINT27)PD3_12") (pintype "bidirectional"))
    )
    (net (code "127") (name "unconnected-(IC1-(XCK0{slash}T0{slash}PCINT8)PB0-Pad40)") (class "Default")
      (node (ref "IC1") (pin "40") (pinfunction "(XCK0/T0/PCINT8)PB0_40") (pintype "bidirectional"))
    )
    (net (code "128") (name "unconnected-(IC1-(XCK1{slash}OC1B{slash}PCINT28)PD4-Pad13)") (class "Default")
      (node (ref "IC1") (pin "13") (pinfunction "(XCK1/OC1B/PCINT28)PD4_13") (pintype "bidirectional"))
    )
    (net (code "129") (name "unconnected-(U10A-QH*-Pad9)") (class "Default")
      (node (ref "U10") (pin "9") (pinfunction "QH*_9") (pintype "tri_state"))
    )
  )
)
